# source_eagle.net
KiCad netlist of a schematic drawn in EAGLE
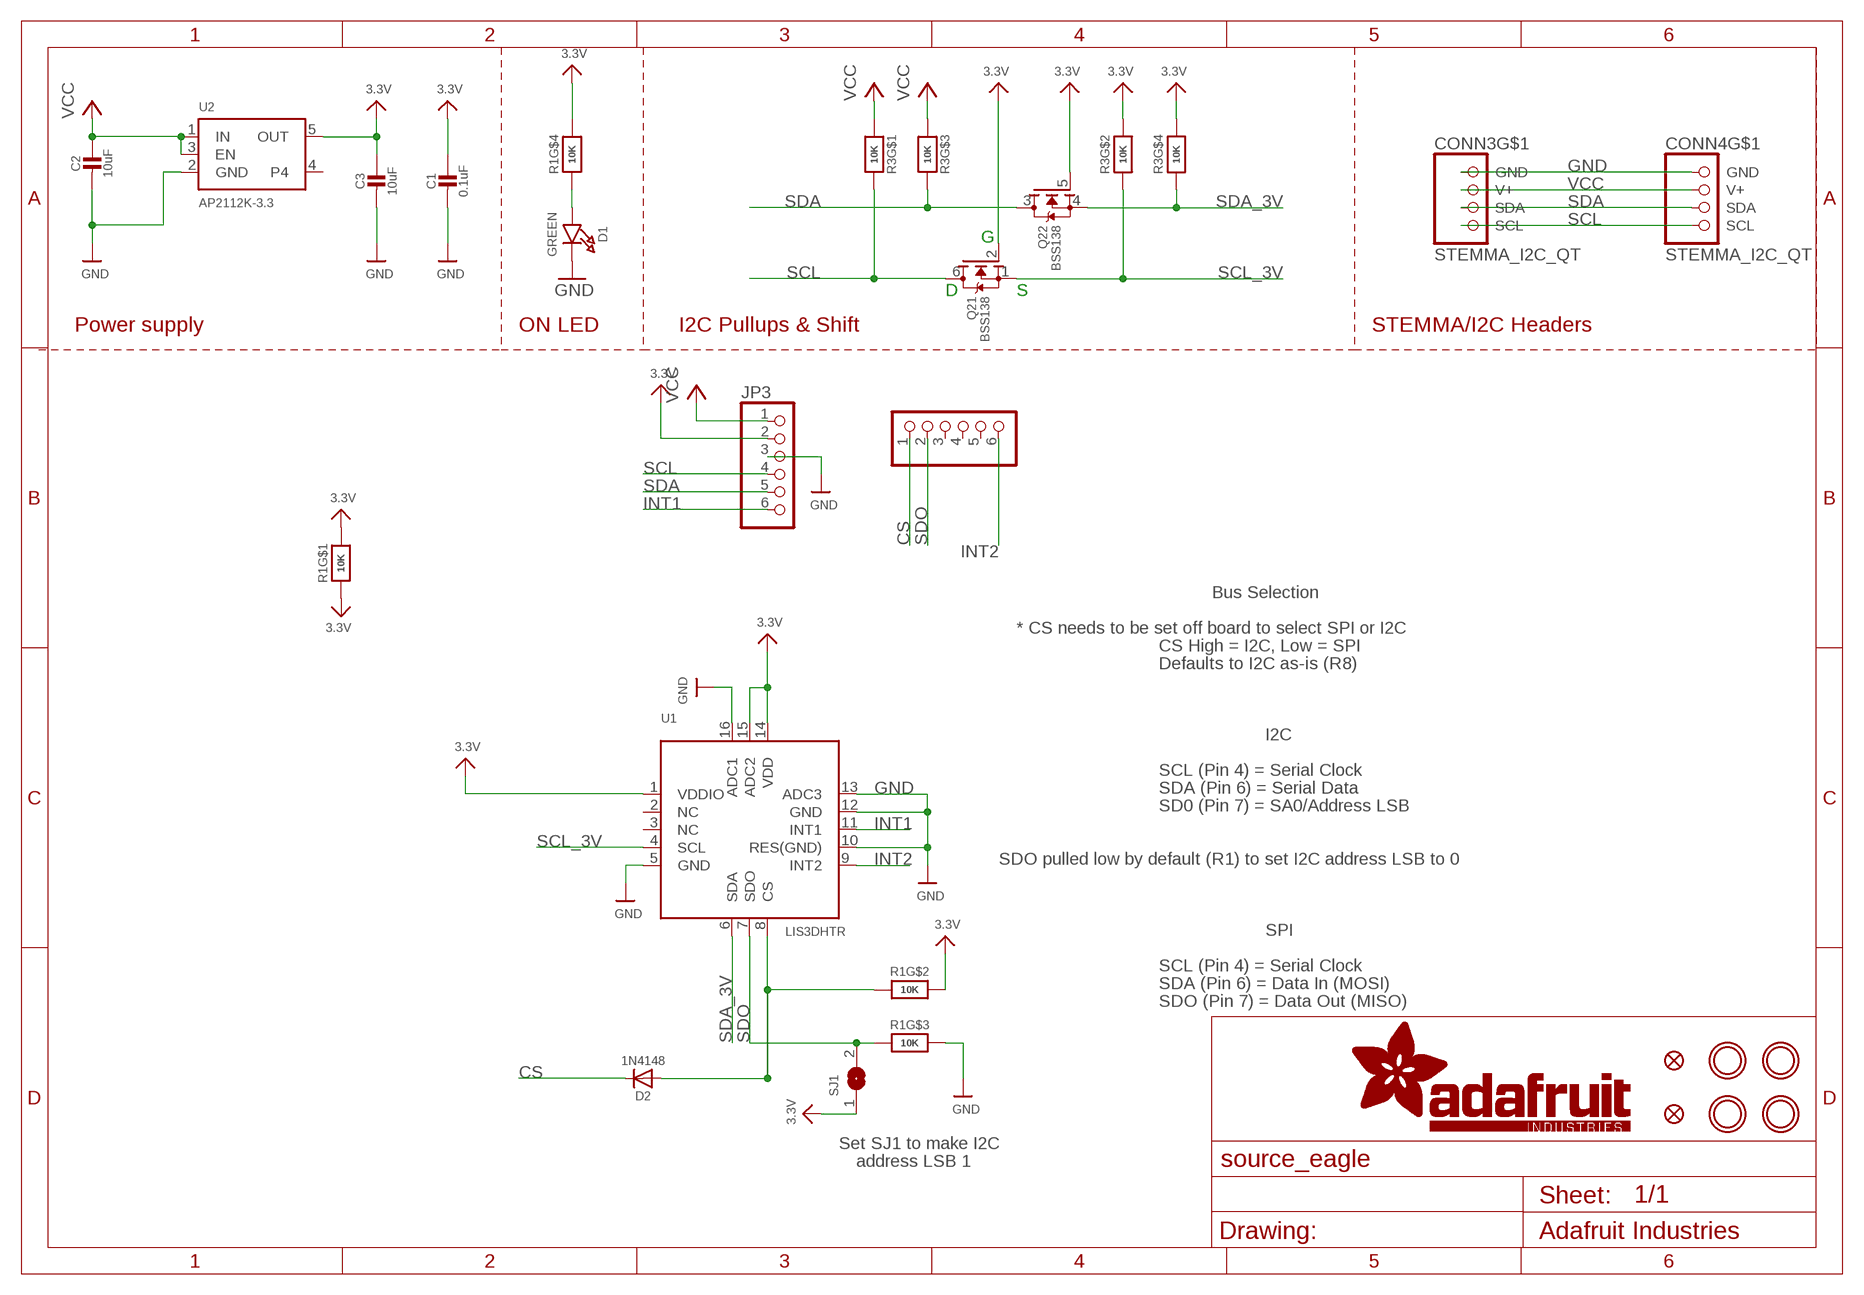
[diagram p0: schematic, sheet 1]

(export (version "E")
  (design (tool "Eeschema 10.0.6"))
  (components
    (comp (ref "C1")
      (value "0.1uF")
      (footprint "eagle-import:0603-NO")
      (libsource (lib "eagle-import") (part "CAP_CERAMIC0603_NO"))
    )
    (comp (ref "C2")
      (value "10uF")
      (footprint "eagle-import:0805-NO")
      (libsource (lib "eagle-import") (part "CAP_CERAMIC0805-NOOUTLINE"))
    )
    (comp (ref "C3")
      (value "10uF")
      (footprint "eagle-import:0805-NO")
      (libsource (lib "eagle-import") (part "CAP_CERAMIC0805-NOOUTLINE"))
    )
    (comp (ref "CONN3")
      (value "STEMMA_I2C_QT")
      (footprint "eagle-import:JST_SH4")
      (libsource (lib "eagle-import") (part "STEMMA_I2C_QT"))
    )
    (comp (ref "CONN4")
      (value "STEMMA_I2C_QT")
      (footprint "eagle-import:JST_SH4")
      (libsource (lib "eagle-import") (part "STEMMA_I2C_QT"))
    )
    (comp (ref "D1")
      (value "GREEN")
      (footprint "eagle-import:CHIPLED_0603_NOOUTLINE")
      (libsource (lib "eagle-import") (part "LED0603_NOOUTLINE"))
    )
    (comp (ref "D2")
      (value "1N4148")
      (footprint "eagle-import:SOD-323")
      (libsource (lib "eagle-import") (part "DIODESOD-323"))
    )
    (comp (ref "FID3")
      (value "FIDUCIAL_1MM")
      (footprint "eagle-import:FIDUCIAL_1MM")
      (libsource (lib "eagle-import") (part "FIDUCIAL_1MM"))
    )
    (comp (ref "FID4")
      (value "FIDUCIAL_1MM")
      (footprint "eagle-import:FIDUCIAL_1MM")
      (libsource (lib "eagle-import") (part "FIDUCIAL_1MM"))
    )
    (comp (ref "JP2")
      (value "HEADER-1X670MIL")
      (footprint "eagle-import:1X06_ROUND_70")
      (libsource (lib "eagle-import") (part "HEADER-1X670MIL"))
    )
    (comp (ref "JP3")
      (value "HEADER-1X670MIL")
      (footprint "eagle-import:1X06_ROUND_70")
      (libsource (lib "eagle-import") (part "HEADER-1X670MIL"))
    )
    (comp (ref "Q2")
      (value "BSS138")
      (footprint "eagle-import:SOT363")
      (libsource (lib "eagle-import") (part "MOSFET-N_DUAL"))
    )
    (comp (ref "R1")
      (value "10K")
      (footprint "eagle-import:RESPACK_4X0603")
      (libsource (lib "eagle-import") (part "RESISTOR_4PACK"))
    )
    (comp (ref "R3")
      (value "10K")
      (footprint "eagle-import:RESPACK_4X0603")
      (libsource (lib "eagle-import") (part "RESISTOR_4PACK"))
    )
    (comp (ref "SJ1")
      (value "SOLDERJUMPER")
      (footprint "eagle-import:SOLDERJUMPER_ARROW_NOPASTE")
      (libsource (lib "eagle-import") (part "SOLDERJUMPER"))
    )
    (comp (ref "U$1")
      (value "MOUNTINGHOLE2.5")
      (footprint "eagle-import:MOUNTINGHOLE_2.5_PLATED")
      (libsource (lib "eagle-import") (part "MOUNTINGHOLE2.5"))
    )
    (comp (ref "U$17")
      (value "MOUNTINGHOLE2.5")
      (footprint "eagle-import:MOUNTINGHOLE_2.5_PLATED")
      (libsource (lib "eagle-import") (part "MOUNTINGHOLE2.5"))
    )
    (comp (ref "U$19")
      (value "MOUNTINGHOLE2.5")
      (footprint "eagle-import:MOUNTINGHOLE_2.5_PLATED")
      (libsource (lib "eagle-import") (part "MOUNTINGHOLE2.5"))
    )
    (comp (ref "U$21")
      (value "MOUNTINGHOLE2.5")
      (footprint "eagle-import:MOUNTINGHOLE_2.5_PLATED")
      (libsource (lib "eagle-import") (part "MOUNTINGHOLE2.5"))
    )
    (comp (ref "U1")
      (value "LIS3DHTR")
      (footprint "eagle-import:LGA16_3X3MM")
      (libsource (lib "eagle-import") (part "ACCEL_LIS3DHTR"))
    )
    (comp (ref "U2")
      (value "AP2112K-3.3")
      (footprint "eagle-import:SOT23-5")
      (libsource (lib "eagle-import") (part "VREG_SOT23-5"))
    )
  )
  (nets
    (net (code "1") (name "/CS") (class "Default")
      (node (ref "D2") (pin "C") (pinfunction "C_C") (pintype "passive"))
      (node (ref "JP2") (pin "1") (pinfunction "1_1") (pintype "passive"))
    )
    (net (code "2") (name "/INT1") (class "Default")
      (node (ref "JP3") (pin "6") (pinfunction "6_6") (pintype "passive"))
      (node (ref "U1") (pin "11") (pinfunction "INT1_11") (pintype "output"))
    )
    (net (code "3") (name "/INT2") (class "Default")
      (node (ref "JP2") (pin "6") (pinfunction "6_6") (pintype "passive"))
      (node (ref "U1") (pin "9") (pinfunction "INT2_9") (pintype "output"))
    )
    (net (code "4") (name "/SCL") (class "Default")
      (node (ref "CONN3") (pin "4") (pinfunction "SCL_4") (pintype "passive"))
      (node (ref "CONN4") (pin "4") (pinfunction "SCL_4") (pintype "passive"))
      (node (ref "JP3") (pin "4") (pinfunction "4_4") (pintype "passive"))
      (node (ref "Q2") (pin "6") (pinfunction "D_6") (pintype "bidirectional"))
      (node (ref "R3") (pin "8") (pinfunction "2_8") (pintype "passive"))
    )
    (net (code "5") (name "/SCL_3V") (class "Default")
      (node (ref "Q2") (pin "1") (pinfunction "S_1") (pintype "bidirectional"))
      (node (ref "R3") (pin "7") (pinfunction "2_7") (pintype "passive"))
      (node (ref "U1") (pin "4") (pinfunction "SCL_4") (pintype "bidirectional"))
    )
    (net (code "6") (name "/SDA") (class "Default")
      (node (ref "CONN3") (pin "3") (pinfunction "SDA_3") (pintype "passive"))
      (node (ref "CONN4") (pin "3") (pinfunction "SDA_3") (pintype "passive"))
      (node (ref "JP3") (pin "5") (pinfunction "5_5") (pintype "passive"))
      (node (ref "Q2") (pin "3") (pinfunction "D_3") (pintype "bidirectional"))
      (node (ref "R3") (pin "6") (pinfunction "2_6") (pintype "passive"))
    )
    (net (code "7") (name "/SDA_3V") (class "Default")
      (node (ref "Q2") (pin "4") (pinfunction "S_4") (pintype "bidirectional"))
      (node (ref "R3") (pin "5") (pinfunction "2_5") (pintype "passive"))
      (node (ref "U1") (pin "6") (pinfunction "SDA_6") (pintype "bidirectional"))
    )
    (net (code "8") (name "/SDO") (class "Default")
      (node (ref "JP2") (pin "2") (pinfunction "2_2") (pintype "passive"))
      (node (ref "R1") (pin "3") (pinfunction "1_3") (pintype "passive"))
      (node (ref "SJ1") (pin "2") (pinfunction "2_2") (pintype "passive"))
      (node (ref "U1") (pin "7") (pinfunction "SDO_7") (pintype "bidirectional"))
    )
    (net (code "9") (name "3.3V") (class "Default")
      (node (ref "C1") (pin "1") (pinfunction "1_1") (pintype "passive"))
      (node (ref "C3") (pin "1") (pinfunction "1_1") (pintype "passive"))
      (node (ref "JP3") (pin "2") (pinfunction "2_2") (pintype "passive"))
      (node (ref "Q2") (pin "2") (pinfunction "G_2") (pintype "bidirectional"))
      (node (ref "Q2") (pin "5") (pinfunction "G_5") (pintype "bidirectional"))
      (node (ref "R1") (pin "1") (pinfunction "1_1") (pintype "passive"))
      (node (ref "R1") (pin "5") (pinfunction "2_5") (pintype "passive"))
      (node (ref "R1") (pin "7") (pinfunction "2_7") (pintype "passive"))
      (node (ref "R1") (pin "8") (pinfunction "2_8") (pintype "passive"))
      (node (ref "R3") (pin "2") (pinfunction "1_2") (pintype "passive"))
      (node (ref "R3") (pin "4") (pinfunction "1_4") (pintype "passive"))
      (node (ref "SJ1") (pin "1") (pinfunction "1_1") (pintype "passive"))
      (node (ref "U1") (pin "1") (pinfunction "VDDIO_1") (pintype "power_in"))
      (node (ref "U1") (pin "14") (pinfunction "VDD_14") (pintype "power_in"))
      (node (ref "U1") (pin "15") (pinfunction "ADC2_15") (pintype "input"))
      (node (ref "U2") (pin "5") (pinfunction "OUT_5") (pintype "power_in"))
    )
    (net (code "10") (name "GND") (class "Default")
      (node (ref "C1") (pin "2") (pinfunction "2_2") (pintype "passive"))
      (node (ref "C2") (pin "2") (pinfunction "2_2") (pintype "passive"))
      (node (ref "C3") (pin "2") (pinfunction "2_2") (pintype "passive"))
      (node (ref "CONN3") (pin "1") (pinfunction "GND_1") (pintype "passive"))
      (node (ref "CONN4") (pin "1") (pinfunction "GND_1") (pintype "passive"))
      (node (ref "D1") (pin "C") (pinfunction "C_C") (pintype "passive"))
      (node (ref "JP3") (pin "3") (pinfunction "3_3") (pintype "passive"))
      (node (ref "R1") (pin "6") (pinfunction "2_6") (pintype "passive"))
      (node (ref "U1") (pin "10") (pinfunction "RES(GND)_10") (pintype "bidirectional"))
      (node (ref "U1") (pin "12") (pinfunction "GND_12") (pintype "power_in"))
      (node (ref "U1") (pin "13") (pinfunction "ADC3_13") (pintype "input"))
      (node (ref "U1") (pin "16") (pinfunction "ADC1_16") (pintype "input"))
      (node (ref "U1") (pin "5") (pinfunction "GND_5") (pintype "power_in"))
      (node (ref "U2") (pin "2") (pinfunction "GND_2") (pintype "power_in"))
    )
    (net (code "11") (name "Net-(R1B-1)") (class "Default")
      (node (ref "D2") (pin "A") (pinfunction "A_A") (pintype "passive"))
      (node (ref "R1") (pin "2") (pinfunction "1_2") (pintype "passive"))
      (node (ref "U1") (pin "8") (pinfunction "CS_8") (pintype "input"))
    )
    (net (code "12") (name "Net-(R1D-1)") (class "Default")
      (node (ref "D1") (pin "A") (pinfunction "A_A") (pintype "passive"))
      (node (ref "R1") (pin "4") (pinfunction "1_4") (pintype "passive"))
    )
    (net (code "13") (name "VCC") (class "Default")
      (node (ref "C2") (pin "1") (pinfunction "1_1") (pintype "passive"))
      (node (ref "CONN3") (pin "2") (pinfunction "V+_2") (pintype "passive"))
      (node (ref "CONN4") (pin "2") (pinfunction "V+_2") (pintype "passive"))
      (node (ref "JP3") (pin "1") (pinfunction "1_1") (pintype "passive"))
      (node (ref "R3") (pin "1") (pinfunction "1_1") (pintype "passive"))
      (node (ref "R3") (pin "3") (pinfunction "1_3") (pintype "passive"))
      (node (ref "U2") (pin "1") (pinfunction "IN_1") (pintype "power_in"))
      (node (ref "U2") (pin "3") (pinfunction "EN_3") (pintype "input"))
    )
    (net (code "14") (name "unconnected-(JP2-Pad3)") (class "Default")
      (node (ref "JP2") (pin "3") (pinfunction "3_3") (pintype "passive"))
    )
    (net (code "15") (name "unconnected-(JP2-Pad4)") (class "Default")
      (node (ref "JP2") (pin "4") (pinfunction "4_4") (pintype "passive"))
    )
    (net (code "16") (name "unconnected-(JP2-Pad5)") (class "Default")
      (node (ref "JP2") (pin "5") (pinfunction "5_5") (pintype "passive"))
    )
    (net (code "17") (name "unconnected-(U1-NC-Pad2)") (class "Default")
      (node (ref "U1") (pin "2") (pinfunction "NC_2") (pintype "no_connect"))
    )
    (net (code "18") (name "unconnected-(U1-NC-Pad3)") (class "Default")
      (node (ref "U1") (pin "3") (pinfunction "NC_3") (pintype "no_connect"))
    )
    (net (code "19") (name "unconnected-(U2-P4-Pad4)") (class "Default")
      (node (ref "U2") (pin "4") (pinfunction "P4_4") (pintype "bidirectional"))
    )
  )
)
